# Receiver_11-15.net
KiCad netlist of a schematic drawn in EAGLE
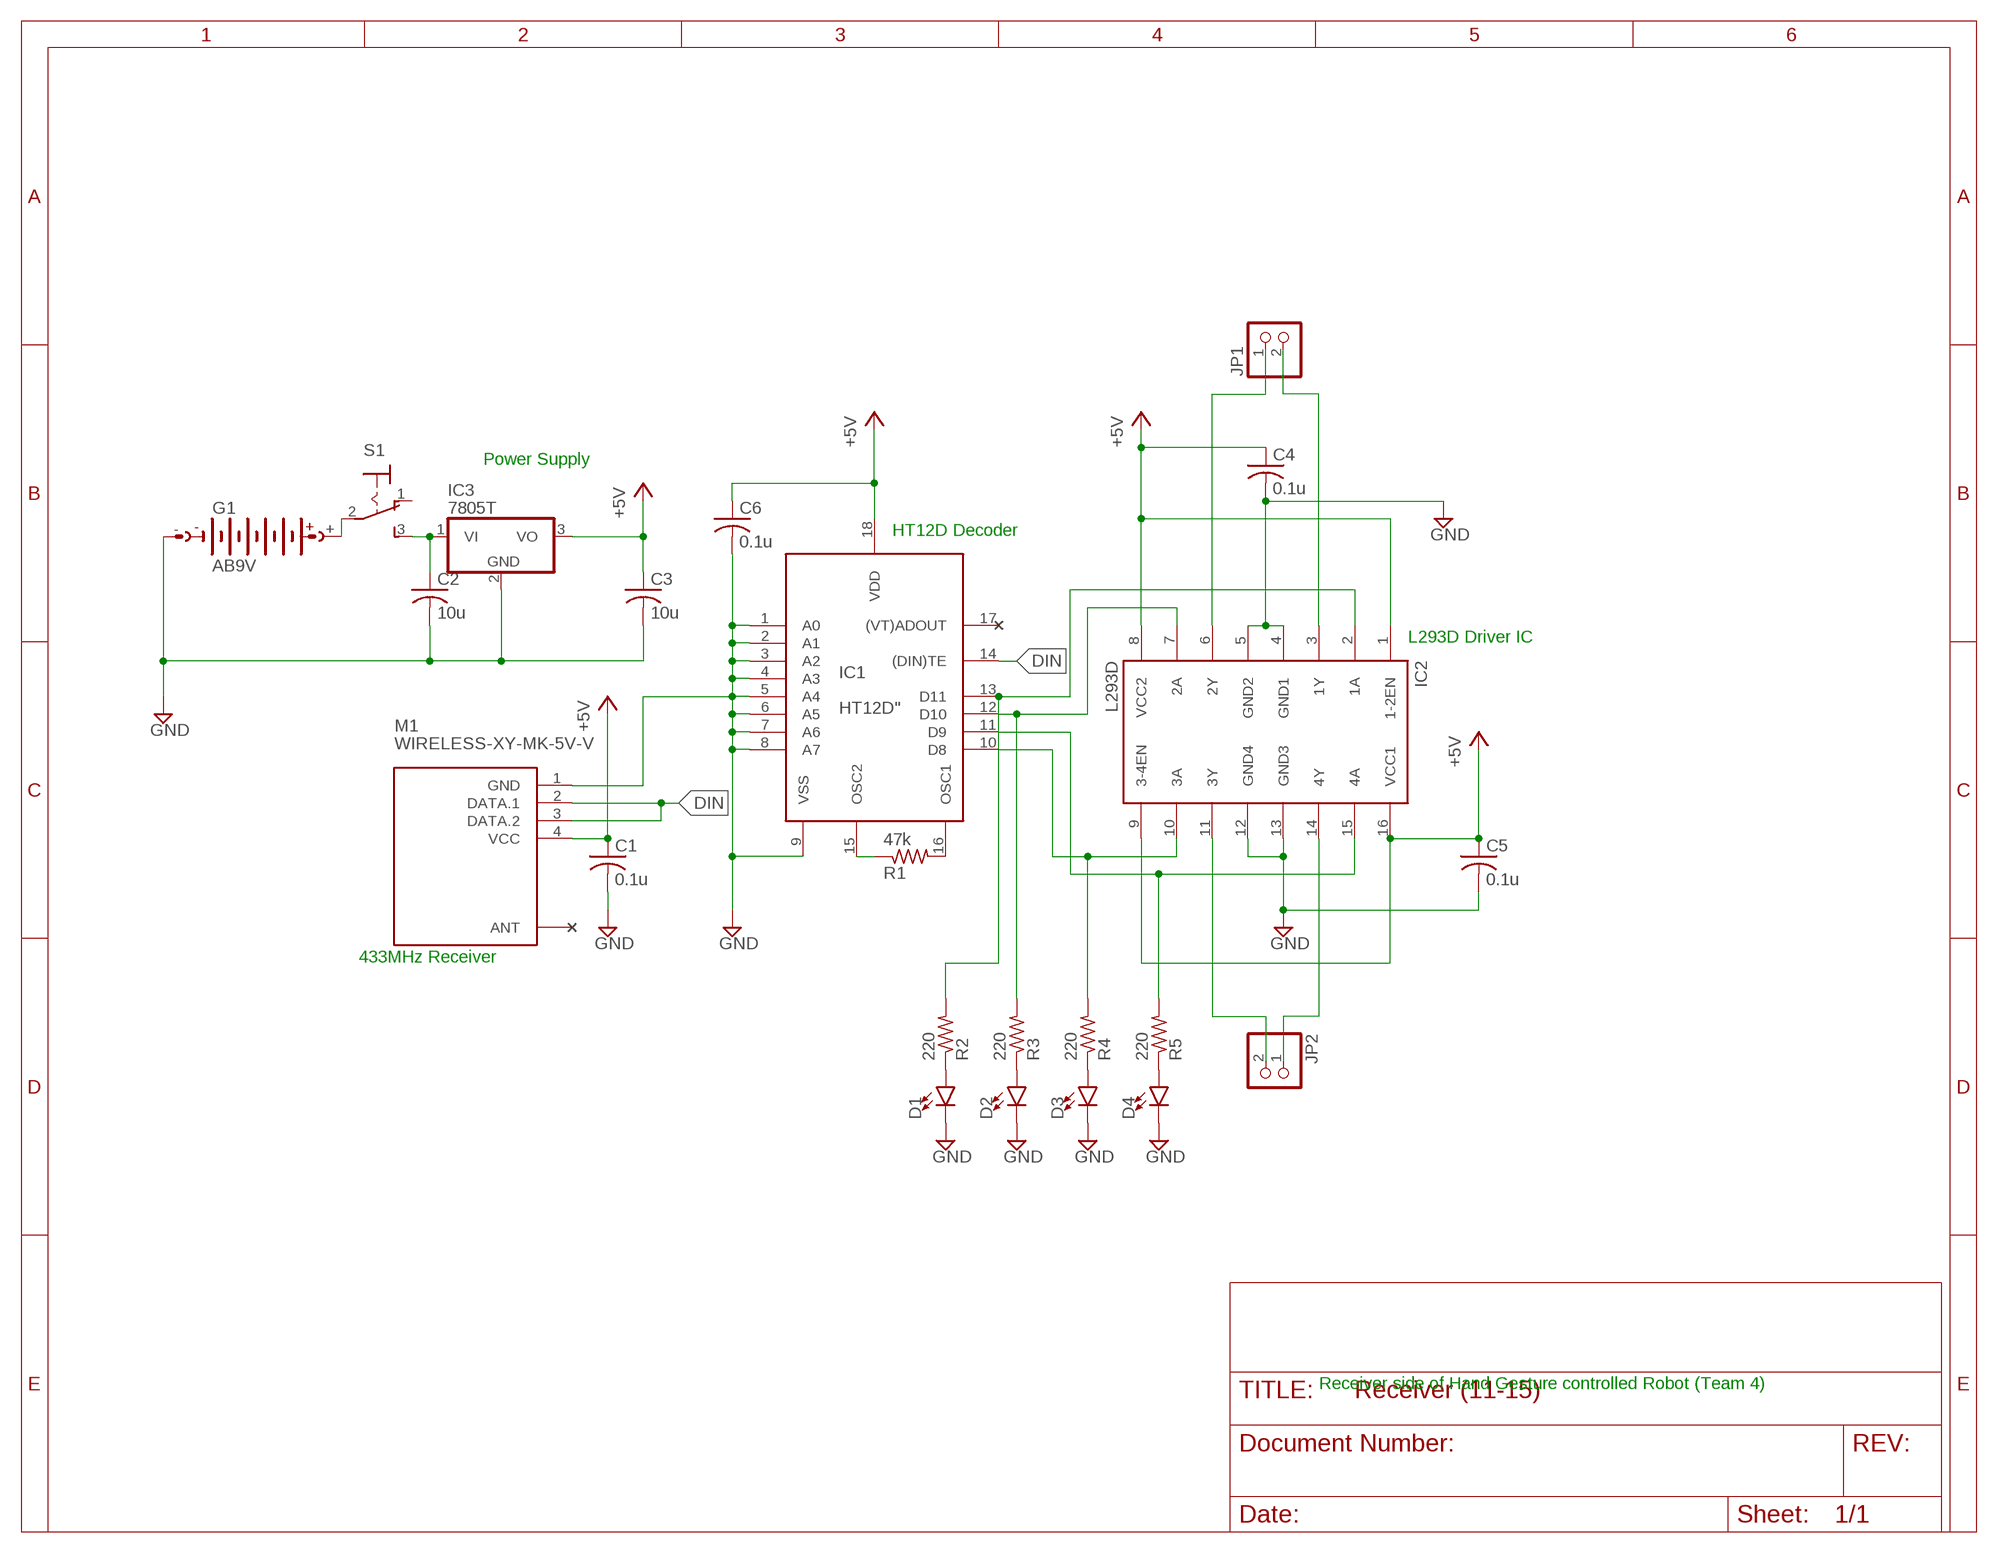
[diagram p0: schematic, sheet 1]

(export (version "E")
  (design (tool "Eeschema 10.0.6"))
  (components
    (comp (ref "C1")
      (value "0.1u")
      (footprint "eagle-import:C0805")
      (libsource (lib "eagle-import") (part "C-USC0805"))
    )
    (comp (ref "C2")
      (value "10u")
      (footprint "eagle-import:C0805")
      (libsource (lib "eagle-import") (part "C-USC0805"))
    )
    (comp (ref "C3")
      (value "10u")
      (footprint "eagle-import:C0805")
      (libsource (lib "eagle-import") (part "C-USC0805"))
    )
    (comp (ref "C4")
      (value "0.1u")
      (footprint "eagle-import:C0805")
      (libsource (lib "eagle-import") (part "C-USC0805"))
    )
    (comp (ref "C5")
      (value "0.1u")
      (footprint "eagle-import:C0805")
      (libsource (lib "eagle-import") (part "C-USC0805"))
    )
    (comp (ref "C6")
      (value "0.1u")
      (footprint "eagle-import:C0805")
      (libsource (lib "eagle-import") (part "C-USC0805"))
    )
    (comp (ref "D1")
      (value "LED3MM")
      (footprint "eagle-import:LED_3MM")
      (libsource (lib "eagle-import") (part "LED3MM"))
    )
    (comp (ref "D2")
      (value "LED3MM")
      (footprint "eagle-import:LED_3MM")
      (libsource (lib "eagle-import") (part "LED3MM"))
    )
    (comp (ref "D3")
      (value "LED3MM")
      (footprint "eagle-import:LED_3MM")
      (libsource (lib "eagle-import") (part "LED3MM"))
    )
    (comp (ref "D4")
      (value "LED3MM")
      (footprint "eagle-import:LED_3MM")
      (libsource (lib "eagle-import") (part "LED3MM"))
    )
    (comp (ref "G1")
      (value "AB9V")
      (footprint "eagle-import:AB9V")
      (libsource (lib "eagle-import") (part "AB9V"))
    )
    (comp (ref "IC1")
      (value "HT12D\"")
      (footprint "eagle-import:18-DIP-A")
      (libsource (lib "eagle-import") (part "HT12D{dblquote}"))
    )
    (comp (ref "IC2")
      (value "L293D")
      (footprint "eagle-import:DIL16")
      (libsource (lib "eagle-import") (part "L293D"))
    )
    (comp (ref "IC3")
      (value "7805T")
      (footprint "eagle-import:TO220H")
      (libsource (lib "eagle-import") (part "78T05"))
    )
    (comp (ref "JP1")
      (value "PINHD-1X2")
      (footprint "eagle-import:1X02")
      (libsource (lib "eagle-import") (part "PINHD-1X2"))
    )
    (comp (ref "JP2")
      (value "PINHD-1X2")
      (footprint "eagle-import:1X02")
      (libsource (lib "eagle-import") (part "PINHD-1X2"))
    )
    (comp (ref "M1")
      (value "WIRELESS-XY-MK-5V-V")
      (footprint "eagle-import:WIRELESS-XY-MK-5V#V")
      (libsource (lib "eagle-import") (part "WIRELESS-XY-MK-5V-V"))
    )
    (comp (ref "R1")
      (value "47k")
      (footprint "eagle-import:R0805")
      (libsource (lib "eagle-import") (part "R-US_R0805"))
    )
    (comp (ref "R2")
      (value "220")
      (footprint "eagle-import:R0805")
      (libsource (lib "eagle-import") (part "R-US_R0805"))
    )
    (comp (ref "R3")
      (value "220")
      (footprint "eagle-import:R0805")
      (libsource (lib "eagle-import") (part "R-US_R0805"))
    )
    (comp (ref "R4")
      (value "220")
      (footprint "eagle-import:R0805")
      (libsource (lib "eagle-import") (part "R-US_R0805"))
    )
    (comp (ref "R5")
      (value "220")
      (footprint "eagle-import:R0805")
      (libsource (lib "eagle-import") (part "R-US_R0805"))
    )
    (comp (ref "S1")
      (value "M9040P")
      (footprint "eagle-import:M9040P")
      (libsource (lib "eagle-import") (part "M9040P"))
    )
  )
  (nets
    (net (code "1") (name "+5V") (class "Default")
      (node (ref "C1") (pin "1") (pinfunction "1_1") (pintype "passive"))
      (node (ref "C3") (pin "1") (pinfunction "1_1") (pintype "passive"))
      (node (ref "C4") (pin "1") (pinfunction "1_1") (pintype "passive"))
      (node (ref "C5") (pin "1") (pinfunction "1_1") (pintype "passive"))
      (node (ref "C6") (pin "1") (pinfunction "1_1") (pintype "passive"))
      (node (ref "IC1") (pin "18") (pinfunction "VDD_18") (pintype "power_in"))
      (node (ref "IC2") (pin "1") (pinfunction "1-2EN_1") (pintype "input"))
      (node (ref "IC2") (pin "16") (pinfunction "VCC1_16") (pintype "power_in"))
      (node (ref "IC2") (pin "8") (pinfunction "VCC2_8") (pintype "power_in"))
      (node (ref "IC2") (pin "9") (pinfunction "3-4EN_9") (pintype "input"))
      (node (ref "IC3") (pin "3") (pinfunction "VO_3") (pintype "passive"))
      (node (ref "M1") (pin "4") (pinfunction "VCC_4") (pintype "bidirectional"))
    )
    (net (code "2") (name "DIN") (class "Default")
      (node (ref "IC1") (pin "14") (pinfunction "(DIN)TE_14") (pintype "input"))
      (node (ref "M1") (pin "2") (pinfunction "DATA.1_2") (pintype "bidirectional"))
      (node (ref "M1") (pin "3") (pinfunction "DATA.2_3") (pintype "bidirectional"))
    )
    (net (code "3") (name "GND") (class "Default")
      (node (ref "C1") (pin "2") (pinfunction "2_2") (pintype "passive"))
      (node (ref "C2") (pin "2") (pinfunction "2_2") (pintype "passive"))
      (node (ref "C3") (pin "2") (pinfunction "2_2") (pintype "passive"))
      (node (ref "C4") (pin "2") (pinfunction "2_2") (pintype "passive"))
      (node (ref "C5") (pin "2") (pinfunction "2_2") (pintype "passive"))
      (node (ref "C6") (pin "2") (pinfunction "2_2") (pintype "passive"))
      (node (ref "D1") (pin "K") (pinfunction "C_K") (pintype "passive"))
      (node (ref "D2") (pin "K") (pinfunction "C_K") (pintype "passive"))
      (node (ref "D3") (pin "K") (pinfunction "C_K") (pintype "passive"))
      (node (ref "D4") (pin "K") (pinfunction "C_K") (pintype "passive"))
      (node (ref "G1") (pin "-") (pinfunction "-_-") (pintype "passive"))
      (node (ref "IC1") (pin "1") (pinfunction "A0_1") (pintype "input"))
      (node (ref "IC1") (pin "2") (pinfunction "A1_2") (pintype "input"))
      (node (ref "IC1") (pin "3") (pinfunction "A2_3") (pintype "input"))
      (node (ref "IC1") (pin "4") (pinfunction "A3_4") (pintype "input"))
      (node (ref "IC1") (pin "5") (pinfunction "A4_5") (pintype "input"))
      (node (ref "IC1") (pin "6") (pinfunction "A5_6") (pintype "input"))
      (node (ref "IC1") (pin "7") (pinfunction "A6_7") (pintype "input"))
      (node (ref "IC1") (pin "8") (pinfunction "A7_8") (pintype "input"))
      (node (ref "IC1") (pin "9") (pinfunction "VSS_9") (pintype "power_in"))
      (node (ref "IC2") (pin "12") (pinfunction "GND4_12") (pintype "power_in"))
      (node (ref "IC2") (pin "13") (pinfunction "GND3_13") (pintype "power_in"))
      (node (ref "IC2") (pin "4") (pinfunction "GND1_4") (pintype "power_in"))
      (node (ref "IC2") (pin "5") (pinfunction "GND2_5") (pintype "power_in"))
      (node (ref "IC3") (pin "2") (pinfunction "GND_2") (pintype "passive"))
      (node (ref "M1") (pin "1") (pinfunction "GND_1") (pintype "bidirectional"))
    )
    (net (code "4") (name "Net-(D1-PadA)") (class "Default")
      (node (ref "D1") (pin "A") (pinfunction "A_A") (pintype "passive"))
      (node (ref "R2") (pin "1") (pinfunction "1_1") (pintype "passive"))
    )
    (net (code "5") (name "Net-(D2-PadA)") (class "Default")
      (node (ref "D2") (pin "A") (pinfunction "A_A") (pintype "passive"))
      (node (ref "R3") (pin "1") (pinfunction "1_1") (pintype "passive"))
    )
    (net (code "6") (name "Net-(D3-PadA)") (class "Default")
      (node (ref "D3") (pin "A") (pinfunction "A_A") (pintype "passive"))
      (node (ref "R4") (pin "1") (pinfunction "1_1") (pintype "passive"))
    )
    (net (code "7") (name "Net-(D4-PadA)") (class "Default")
      (node (ref "D4") (pin "A") (pinfunction "A_A") (pintype "passive"))
      (node (ref "R5") (pin "1") (pinfunction "1_1") (pintype "passive"))
    )
    (net (code "8") (name "Net-(IC1-D8)") (class "Default")
      (node (ref "IC1") (pin "10") (pinfunction "D8_10") (pintype "output"))
      (node (ref "IC2") (pin "10") (pinfunction "3A_10") (pintype "input"))
      (node (ref "R4") (pin "2") (pinfunction "2_2") (pintype "passive"))
    )
    (net (code "9") (name "Net-(IC1-D9)") (class "Default")
      (node (ref "IC1") (pin "11") (pinfunction "D9_11") (pintype "output"))
      (node (ref "IC2") (pin "15") (pinfunction "4A_15") (pintype "input"))
      (node (ref "R5") (pin "2") (pinfunction "2_2") (pintype "passive"))
    )
    (net (code "10") (name "Net-(IC1-D10)") (class "Default")
      (node (ref "IC1") (pin "12") (pinfunction "D10_12") (pintype "output"))
      (node (ref "IC2") (pin "7") (pinfunction "2A_7") (pintype "input"))
      (node (ref "R3") (pin "2") (pinfunction "2_2") (pintype "passive"))
    )
    (net (code "11") (name "Net-(IC1-D11)") (class "Default")
      (node (ref "IC1") (pin "13") (pinfunction "D11_13") (pintype "output"))
      (node (ref "IC2") (pin "2") (pinfunction "1A_2") (pintype "input"))
      (node (ref "R2") (pin "2") (pinfunction "2_2") (pintype "passive"))
    )
    (net (code "12") (name "Net-(IC1-OSC1)") (class "Default")
      (node (ref "IC1") (pin "16") (pinfunction "OSC1_16") (pintype "input"))
      (node (ref "R1") (pin "2") (pinfunction "2_2") (pintype "passive"))
    )
    (net (code "13") (name "Net-(IC1-OSC2)") (class "Default")
      (node (ref "IC1") (pin "15") (pinfunction "OSC2_15") (pintype "output"))
      (node (ref "R1") (pin "1") (pinfunction "1_1") (pintype "passive"))
    )
    (net (code "14") (name "Net-(IC2-1Y)") (class "Default")
      (node (ref "IC2") (pin "3") (pinfunction "1Y_3") (pintype "output"))
      (node (ref "JP1") (pin "2") (pinfunction "2_2") (pintype "passive"))
    )
    (net (code "15") (name "Net-(IC2-2Y)") (class "Default")
      (node (ref "IC2") (pin "6") (pinfunction "2Y_6") (pintype "output"))
      (node (ref "JP1") (pin "1") (pinfunction "1_1") (pintype "passive"))
    )
    (net (code "16") (name "Net-(IC2-3Y)") (class "Default")
      (node (ref "IC2") (pin "11") (pinfunction "3Y_11") (pintype "output"))
      (node (ref "JP2") (pin "2") (pinfunction "2_2") (pintype "passive"))
    )
    (net (code "17") (name "Net-(IC2-4Y)") (class "Default")
      (node (ref "IC2") (pin "14") (pinfunction "4Y_14") (pintype "output"))
      (node (ref "JP2") (pin "1") (pinfunction "1_1") (pintype "passive"))
    )
    (net (code "18") (name "Net-(IC3-VI)") (class "Default")
      (node (ref "C2") (pin "1") (pinfunction "1_1") (pintype "passive"))
      (node (ref "IC3") (pin "1") (pinfunction "VI_1") (pintype "input"))
      (node (ref "S1") (pin "3") (pinfunction "S_3") (pintype "passive"))
    )
    (net (code "19") (name "Net-(S1-P)") (class "Default")
      (node (ref "G1") (pin "+") (pinfunction "+_+") (pintype "passive"))
      (node (ref "S1") (pin "2") (pinfunction "P_2") (pintype "passive"))
    )
    (net (code "20") (name "unconnected-(IC1-(VT)ADOUT-Pad17)") (class "Default")
      (node (ref "IC1") (pin "17") (pinfunction "(VT)ADOUT_17") (pintype "output"))
    )
    (net (code "21") (name "unconnected-(M1-PadANT)") (class "Default")
      (node (ref "M1") (pin "ANT") (pinfunction "ANT_ANT") (pintype "output"))
    )
    (net (code "22") (name "unconnected-(S1-O-Pad1)") (class "Default")
      (node (ref "S1") (pin "1") (pinfunction "O_1") (pintype "passive"))
    )
  )
)
